# Fujin_Connectors.net
KiCad netlist of a schematic drawn in Altium Designer
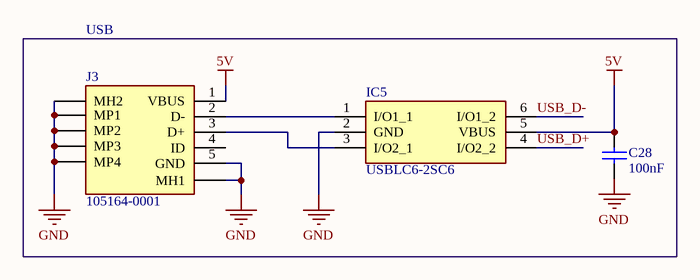
[diagram p0: Fujin_Connectors.SchDoc]

(export (version "E")
  (design (tool "Eeschema 10.0.6"))
  (components
    (comp (ref "C28")
      (value "100nF")
      (footprint "CAP 0402")
      (description "Capacitor Cer 100nF 50V 0402")
      (fields (field (name "MANUFACTURER PART NUMBER") "IMP14925"))
      (libsource (lib "FujinLib") (part "CAP 100NF 50V 0402"))
    )
    (comp (ref "IC5")
      (value "USBLC6-2SC6")
      (footprint "SOT95P280X145-6N")
      (description "Integrated Circuit")
      (fields (field (name "MOUSER PART NUMBER") "511-USBLC6-2SC6"))
      (libsource (lib "FujinLib") (part "USBLC6-2SC6"))
    )
    (comp (ref "J3")
      (value "105164-0001")
      (footprint "SamacSys:1051640001")
      (description "Connector")
      (fields (field (name "MOUSER PART NUMBER") "538-105164-0001"))
      (libsource (lib "FujinLib") (part "105164-0001"))
    )
  )
  (nets
    (net (code "1") (name "/USB_D+") (class "Default")
      (node (ref "IC5") (pin "4") (pinfunction "I/O2_2_4") (pintype "passive"))
    )
    (net (code "2") (name "/USB_D-") (class "Default")
      (node (ref "IC5") (pin "6") (pinfunction "I/O1_2_6") (pintype "passive"))
    )
    (net (code "3") (name "5V") (class "Default")
      (node (ref "C28") (pin "2") (pinfunction "2_2") (pintype "passive"))
      (node (ref "IC5") (pin "5") (pinfunction "VBUS_5") (pintype "passive"))
      (node (ref "J3") (pin "1") (pinfunction "VBUS_1") (pintype "passive"))
    )
    (net (code "4") (name "GND") (class "Default")
      (node (ref "C28") (pin "1") (pinfunction "1_1") (pintype "passive"))
      (node (ref "IC5") (pin "2") (pinfunction "GND_2") (pintype "passive"))
      (node (ref "J3") (pin "5") (pinfunction "GND_5") (pintype "passive"))
      (node (ref "J3") (pin "MH1") (pinfunction "MH1_MH1") (pintype "passive"))
      (node (ref "J3") (pin "MH2") (pinfunction "MH2_MH2") (pintype "passive"))
      (node (ref "J3") (pin "MP1") (pinfunction "MP1_MP1") (pintype "passive"))
      (node (ref "J3") (pin "MP2") (pinfunction "MP2_MP2") (pintype "passive"))
      (node (ref "J3") (pin "MP3") (pinfunction "MP3_MP3") (pintype "passive"))
      (node (ref "J3") (pin "MP4") (pinfunction "MP4_MP4") (pintype "passive"))
    )
    (net (code "5") (name "Net-(IC5-I{slash}O1_1)") (class "Default")
      (node (ref "IC5") (pin "1") (pinfunction "I/O1_1_1") (pintype "passive"))
      (node (ref "J3") (pin "2") (pinfunction "D-_2") (pintype "passive"))
    )
    (net (code "6") (name "Net-(IC5-I{slash}O2_1)") (class "Default")
      (node (ref "IC5") (pin "3") (pinfunction "I/O2_1_3") (pintype "passive"))
      (node (ref "J3") (pin "3") (pinfunction "D+_3") (pintype "passive"))
    )
    (net (code "7") (name "unconnected-(J3-ID-Pad4)") (class "Default")
      (node (ref "J3") (pin "4") (pinfunction "ID_4") (pintype "passive"))
    )
  )
)
